# NegativeRegulator.net
KiCad netlist of a schematic drawn in Altium Designer
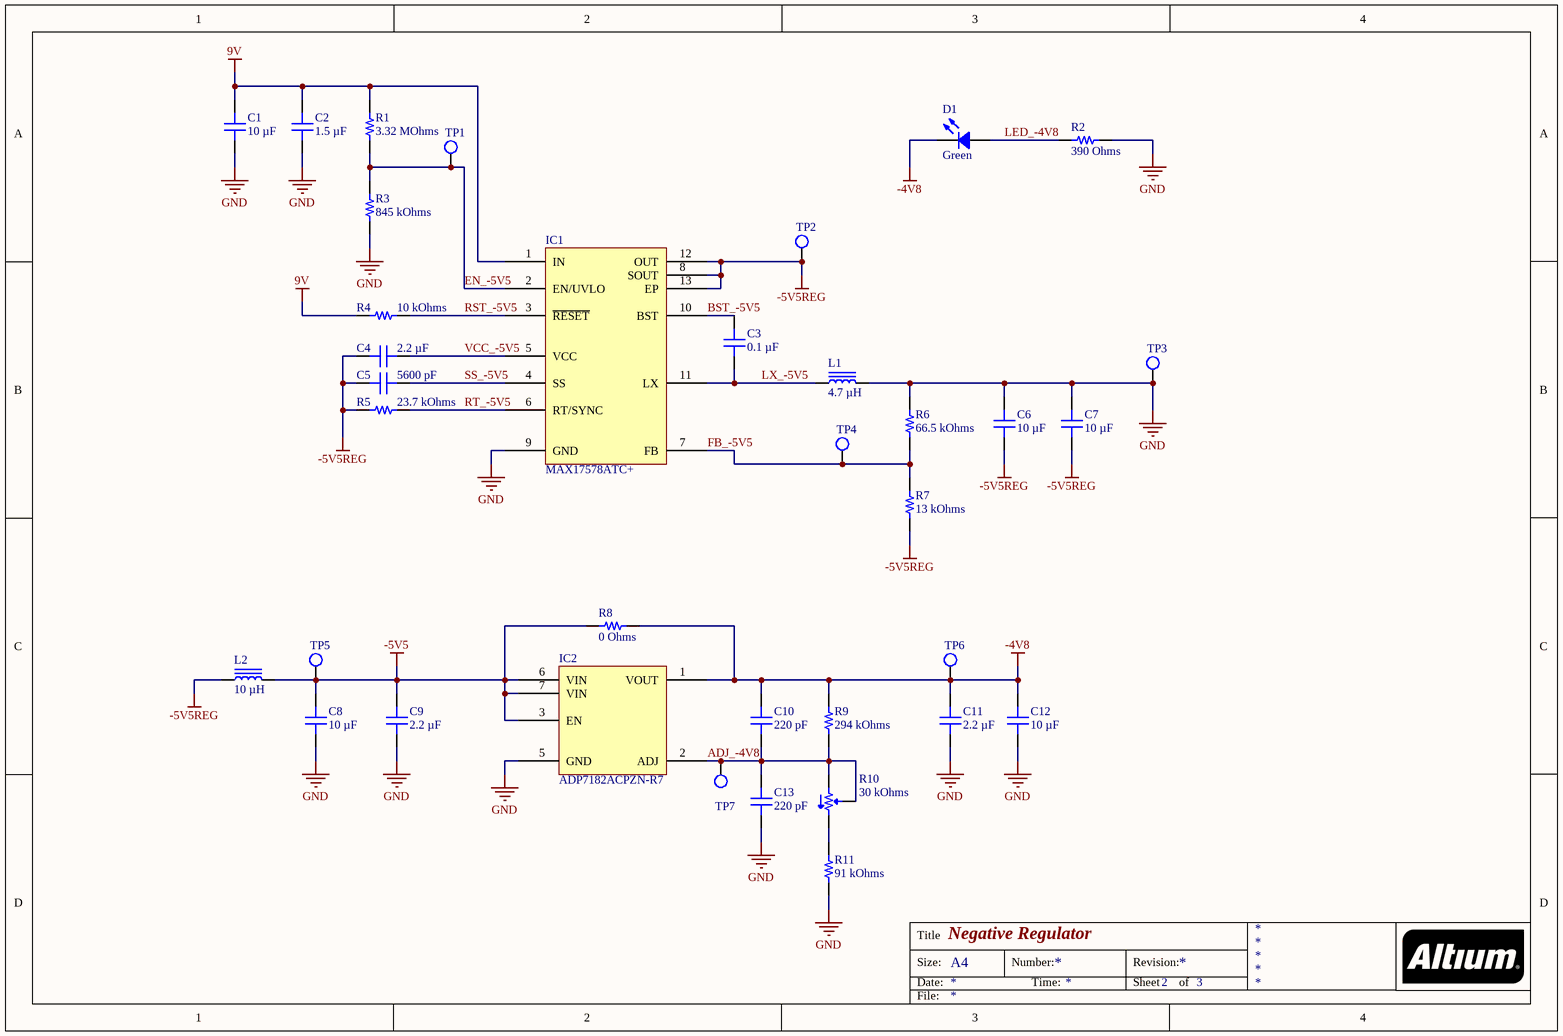
[diagram p0: NegativeRegulator.SchDoc]

(export (version "E")
  (design (tool "Eeschema 10.0.6"))
  (components
    (comp (ref "C1")
      (value "10 µF")
      (footprint "CAP 1206_3216 - 0.8MM")
      (description "CAP CER 10UF 35V X5R 1206")
      (fields (field (name "PART NUMBER") "GMK316BJ106KL-T") (field (name "MANUFACTURER") "Taiyo Yuden"))
      (libsource (lib "altiumlibrary.com") (part "Capacitor"))
    )
    (comp (ref "C2")
      (value "1.5 µF")
      (footprint "CAP 1206_3216 - 0.8MM")
      (description "CAP CER 1.5UF 16V X7R 1206")
      (fields (field (name "PART NUMBER") "C1206C155K4RAC7800") (field (name "MANUFACTURER") "KEMET"))
      (libsource (lib "altiumlibrary.com") (part "Capacitor"))
    )
    (comp (ref "C3")
      (value "0.1 µF")
      (footprint "CAP 0603_1608")
      (description "CAP CER 0.1UF 16V X7R 0603")
      (fields
        (field (name "PART NUMBER") "CL10B104KO8NNNC")
        (field (name "MANUFACTURER") "Samsung Electro-Mechanics")
      )
      (libsource (lib "altiumlibrary.com") (part "Capacitor"))
    )
    (comp (ref "C4")
      (value "2.2 µF")
      (footprint "CAP 0805_2012")
      (description "CAP CER 2.2UF 25V X7R 0805")
      (fields
        (field (name "PART NUMBER") "GRM21BR71E225KE11L")
        (field (name "MANUFACTURER") "Murata Electronics")
      )
      (libsource (lib "altiumlibrary.com") (part "Capacitor"))
    )
    (comp (ref "C5")
      (value "5600 pF")
      (footprint "CAP 0603_1608")
      (description "CAP CER 5600PF 50V X7R 0603")
      (fields (field (name "PART NUMBER") "C0603C562K5RAC7867") (field (name "MANUFACTURER") "KEMET"))
      (libsource (lib "altiumlibrary.com") (part "Capacitor"))
    )
    (comp (ref "C6")
      (value "10 µF")
      (footprint "CAP 1206_3216 - 0.8MM")
      (description "CAP CER 10UF 35V X5R 1206")
      (fields (field (name "PART NUMBER") "GMK316BJ106KL-T") (field (name "MANUFACTURER") "Taiyo Yuden"))
      (libsource (lib "altiumlibrary.com") (part "Capacitor"))
    )
    (comp (ref "C7")
      (value "10 µF")
      (footprint "CAP 1206_3216 - 0.8MM")
      (description "CAP CER 10UF 35V X5R 1206")
      (fields (field (name "PART NUMBER") "GMK316BJ106KL-T") (field (name "MANUFACTURER") "Taiyo Yuden"))
      (libsource (lib "altiumlibrary.com") (part "Capacitor"))
    )
    (comp (ref "C8")
      (value "10 µF")
      (footprint "CAP 1206_3216 - 0.8MM")
      (description "CAP CER 10UF 35V X5R 1206")
      (fields (field (name "PART NUMBER") "GMK316BJ106KL-T") (field (name "MANUFACTURER") "Taiyo Yuden"))
      (libsource (lib "altiumlibrary.com") (part "Capacitor"))
    )
    (comp (ref "C9")
      (value "2.2 µF")
      (footprint "CAP 0805_2012")
      (description "CAP CER 2.2UF 25V X7R 0805")
      (fields
        (field (name "PART NUMBER") "GRM21BR71E225KE11L")
        (field (name "MANUFACTURER") "Murata Electronics")
      )
      (libsource (lib "altiumlibrary.com") (part "Capacitor"))
    )
    (comp (ref "C10")
      (value "220 pF")
      (footprint "CAP 0603_1608")
      (description "CAP CER 220PF 25V C0G/NPO 0603")
      (fields (field (name "PART NUMBER") "CC0603JRNPO8BN221") (field (name "MANUFACTURER") "Yageo"))
      (libsource (lib "altiumlibrary.com") (part "Capacitor"))
    )
    (comp (ref "C11")
      (value "2.2 µF")
      (footprint "CAP 0805_2012")
      (description "CAP CER 2.2UF 25V X7R 0805")
      (fields
        (field (name "PART NUMBER") "GRM21BR71E225KE11L")
        (field (name "MANUFACTURER") "Murata Electronics")
      )
      (libsource (lib "altiumlibrary.com") (part "Capacitor"))
    )
    (comp (ref "C12")
      (value "10 µF")
      (footprint "CAP 1206_3216 - 0.8MM")
      (description "CAP CER 10UF 35V X5R 1206")
      (fields (field (name "PART NUMBER") "GMK316BJ106KL-T") (field (name "MANUFACTURER") "Taiyo Yuden"))
      (libsource (lib "altiumlibrary.com") (part "Capacitor"))
    )
    (comp (ref "C13")
      (value "220 pF")
      (footprint "CAP 0603_1608")
      (description "CAP CER 220PF 25V C0G/NPO 0603")
      (fields (field (name "PART NUMBER") "CC0603JRNPO8BN221") (field (name "MANUFACTURER") "Yageo"))
      (libsource (lib "altiumlibrary.com") (part "Capacitor"))
    )
    (comp (ref "D1")
      (value "Green")
      (footprint "LED 0805_2012 GREEN")
      (description "LED GREEN CLEAR CHIP SMD")
      (fields (field (name "PART NUMBER") "APHCM2012CGCK-F01") (field (name "MANUFACTURER") "Kingbright"))
      (libsource (lib "altiumlibrary.com") (part "LED"))
    )
    (comp (ref "IC1")
      (value "MAX17578ATC+")
      (footprint "MAXIM TDFN-12 3X3MM TD1233+1")
      (description "4.5V TO 60V, 1A HIGH-EFFICIENCY,")
      (fields (field (name "MANUFACTURER") "Analog Devices Inc./Maxim Integrated"))
      (libsource (lib "altiumlibrary.com") (part "MAXIM MAX17578"))
    )
    (comp (ref "IC2")
      (value "ADP7182ACPZN-R7")
      (footprint "AD LFCSP-6 2X2MM CP-6-3")
      (description "IC REG LIN NEG ADJ 200MA 6LFCSP")
      (fields (field (name "MANUFACTURER") "Analog Devices Inc."))
      (libsource (lib "altiumlibrary.com") (part "AD ADP7182 LFCSP6 ADJ"))
    )
    (comp (ref "L1")
      (value "4.7 µH")
      (footprint "WURTH WE-HCI 7040")
      (description "FIXED IND 4.7UH 6A 19.5 MOHM SMD")
      (fields (field (name "PART NUMBER") "744311470") (field (name "MANUFACTURER") "Würth Elektronik"))
      (libsource (lib "altiumlibrary.com") (part "Inductor"))
    )
    (comp (ref "L2")
      (value "10 µH")
      (footprint "TAIYO YUDEN NR4018")
      (description "FIXED IND 10UH 840MA 216MOHM SMD")
      (fields (field (name "PART NUMBER") "NR4018T100M") (field (name "MANUFACTURER") "Taiyo Yuden"))
      (libsource (lib "altiumlibrary.com") (part "Inductor"))
    )
    (comp (ref "R1")
      (value "3.32 MOhms")
      (footprint "RES 0603_1608")
      (description "RES 3.32M OHM 1% 1/10W 0603")
      (fields (field (name "PART NUMBER") "RC0603FR-073M32L") (field (name "MANUFACTURER") "Yageo"))
      (libsource (lib "altiumlibrary.com") (part "Resistor"))
    )
    (comp (ref "R2")
      (value "390 Ohms")
      (footprint "RES 0805_2012")
      (description "RES SMD 390 OHM 1% 1/8W 0805")
      (fields
        (field (name "PART NUMBER") "CRG0805F390R")
        (field (name "MANUFACTURER") "TE Connectivity Passive Product")
      )
      (libsource (lib "altiumlibrary.com") (part "Resistor"))
    )
    (comp (ref "R3")
      (value "845 kOhms")
      (footprint "RES 0603_1608")
      (description "RES 845K OHM 1% 1/10W 0603")
      (fields (field (name "PART NUMBER") "RC0603FR-07845KL") (field (name "MANUFACTURER") "Yageo"))
      (libsource (lib "altiumlibrary.com") (part "Resistor"))
    )
    (comp (ref "R4")
      (value "10 kOhms")
      (footprint "RES 0603_1608")
      (description "RES 10K OHM 1% 1/10W 0603")
      (fields (field (name "PART NUMBER") "RC0603FR-0710KL") (field (name "MANUFACTURER") "Yageo"))
      (libsource (lib "altiumlibrary.com") (part "Resistor"))
    )
    (comp (ref "R5")
      (value "23.7 kOhms")
      (footprint "RES 0603_1608")
      (description "RES 23.7K OHM 1% 1/10W 0603")
      (fields (field (name "PART NUMBER") "RC0603FR-0723K7L") (field (name "MANUFACTURER") "Yageo"))
      (libsource (lib "altiumlibrary.com") (part "Resistor"))
    )
    (comp (ref "R6")
      (value "66.5 kOhms")
      (footprint "RES 0603_1608")
      (description "RES SMD 66.5K OHM 1% 1/10W 0603")
      (fields
        (field (name "PART NUMBER") "ERJ-3EKF6652V")
        (field (name "MANUFACTURER") "Panasonic Electronic Components")
      )
      (libsource (lib "altiumlibrary.com") (part "Resistor"))
    )
    (comp (ref "R7")
      (value "13 kOhms")
      (footprint "RES 0603_1608")
      (description "RES SMD 13K OHM 5% 1/10W 0603")
      (fields
        (field (name "PART NUMBER") "ERJ-3GEYJ133V")
        (field (name "MANUFACTURER") "Panasonic Electronic Components")
      )
      (libsource (lib "altiumlibrary.com") (part "Resistor"))
    )
    (comp (ref "R8")
      (value "0 Ohms")
      (footprint "RES 0805_2012")
      (description "RES 0 OHM JUMPER 1/4W 0805")
      (fields (field (name "PART NUMBER") "RC0805JR-7W0RL") (field (name "MANUFACTURER") "Yageo"))
      (libsource (lib "altiumlibrary.com") (part "Resistor"))
    )
    (comp (ref "R9")
      (value "294 kOhms")
      (footprint "RES 0603_1608")
      (description "RES SMD 294K OHM 0.1% 1/10W 0603")
      (fields
        (field (name "PART NUMBER") "ERA-3AEB2943V")
        (field (name "MANUFACTURER") "Panasonic Electronic Components")
      )
      (libsource (lib "altiumlibrary.com") (part "Resistor"))
    )
    (comp (ref "R10")
      (value "30 kOhms")
      (footprint "POT BOURNS TRIMPOT TC33")
      (description "TRIMMER 30K OHM 0.1W J LEAD TOP")
      (fields (field (name "PART NUMBER") "TC33X-2-303E") (field (name "MANUFACTURER") "Bourns Inc."))
      (libsource (lib "altiumlibrary.com") (part "Potentiometer"))
    )
    (comp (ref "R11")
      (value "91 kOhms")
      (footprint "RES 0603_1608")
      (description "RES 91K OHM 1% 1/10W 0603")
      (fields (field (name "PART NUMBER") "RC0603FR-0791KL") (field (name "MANUFACTURER") "Yageo"))
      (libsource (lib "altiumlibrary.com") (part "Resistor"))
    )
    (comp (ref "TP1")
      (value "Test Point")
      (footprint "TestPoint-1.5mm")
      (libsource (lib "Original Circuit") (part "Test Point"))
    )
    (comp (ref "TP2")
      (value "Test Point")
      (footprint "TestPoint-1.5mm")
      (libsource (lib "Original Circuit") (part "Test Point"))
    )
    (comp (ref "TP3")
      (value "Test Point")
      (footprint "TestPoint-1.5mm")
      (libsource (lib "Original Circuit") (part "Test Point"))
    )
    (comp (ref "TP4")
      (value "Test Point")
      (footprint "TestPoint-1.5mm")
      (libsource (lib "Original Circuit") (part "Test Point"))
    )
    (comp (ref "TP5")
      (value "Test Point")
      (footprint "TestPoint-1.5mm")
      (libsource (lib "Original Circuit") (part "Test Point"))
    )
    (comp (ref "TP6")
      (value "Test Point")
      (footprint "TestPoint-1.5mm")
      (libsource (lib "Original Circuit") (part "Test Point"))
    )
    (comp (ref "TP7")
      (value "Test Point")
      (footprint "TestPoint-1.5mm")
      (libsource (lib "Original Circuit") (part "Test Point"))
    )
  )
  (nets
    (net (code "1") (name "-4V8") (class "Default")
      (node (ref "C10") (pin "2") (pinfunction "2_2") (pintype "passive"))
      (node (ref "C11") (pin "2") (pinfunction "2_2") (pintype "passive"))
      (node (ref "C12") (pin "2") (pinfunction "2_2") (pintype "passive"))
      (node (ref "D1") (pin "2") (pinfunction "2_2") (pintype "passive"))
      (node (ref "IC2") (pin "1") (pinfunction "VOUT_1") (pintype "passive"))
      (node (ref "R8") (pin "2") (pinfunction "2_2") (pintype "passive"))
      (node (ref "R9") (pin "2") (pinfunction "2_2") (pintype "passive"))
      (node (ref "TP6") (pin "1") (pinfunction "TP_1") (pintype "passive"))
    )
    (net (code "2") (name "-5V5") (class "Default")
      (node (ref "C8") (pin "2") (pinfunction "2_2") (pintype "passive"))
      (node (ref "C9") (pin "2") (pinfunction "2_2") (pintype "passive"))
      (node (ref "IC2") (pin "3") (pinfunction "EN_3") (pintype "passive"))
      (node (ref "IC2") (pin "6") (pinfunction "VIN_6") (pintype "passive"))
      (node (ref "IC2") (pin "7") (pinfunction "VIN_7") (pintype "passive"))
      (node (ref "L2") (pin "2") (pinfunction "2_2") (pintype "passive"))
      (node (ref "R8") (pin "1") (pinfunction "1_1") (pintype "passive"))
      (node (ref "TP5") (pin "1") (pinfunction "TP_1") (pintype "passive"))
    )
    (net (code "3") (name "-5V5REG") (class "Default")
      (node (ref "C4") (pin "1") (pinfunction "1_1") (pintype "passive"))
      (node (ref "C5") (pin "1") (pinfunction "1_1") (pintype "passive"))
      (node (ref "C6") (pin "1") (pinfunction "1_1") (pintype "passive"))
      (node (ref "C7") (pin "1") (pinfunction "1_1") (pintype "passive"))
      (node (ref "IC1") (pin "12") (pinfunction "OUT_12") (pintype "passive"))
      (node (ref "IC1") (pin "13") (pinfunction "EP_13") (pintype "passive"))
      (node (ref "IC1") (pin "8") (pinfunction "SOUT_8") (pintype "passive"))
      (node (ref "L2") (pin "1") (pinfunction "1_1") (pintype "passive"))
      (node (ref "R5") (pin "1") (pinfunction "1_1") (pintype "passive"))
      (node (ref "R7") (pin "1") (pinfunction "1_1") (pintype "passive"))
      (node (ref "TP2") (pin "1") (pinfunction "TP_1") (pintype "passive"))
    )
    (net (code "4") (name "/ADJ_-4V8") (class "Default")
      (node (ref "C10") (pin "1") (pinfunction "1_1") (pintype "passive"))
      (node (ref "C13") (pin "2") (pinfunction "2_2") (pintype "passive"))
      (node (ref "IC2") (pin "2") (pinfunction "ADJ_2") (pintype "passive"))
      (node (ref "R10") (pin "1") (pinfunction "1_1") (pintype "passive"))
      (node (ref "R10") (pin "2") (pinfunction "2_2") (pintype "passive"))
      (node (ref "R9") (pin "1") (pinfunction "1_1") (pintype "passive"))
      (node (ref "TP7") (pin "1") (pinfunction "TP_1") (pintype "passive"))
    )
    (net (code "5") (name "/BST_-5V5") (class "Default")
      (node (ref "C3") (pin "2") (pinfunction "2_2") (pintype "passive"))
      (node (ref "IC1") (pin "10") (pinfunction "BST_10") (pintype "passive"))
    )
    (net (code "6") (name "/EN_-5V5") (class "Default")
      (node (ref "IC1") (pin "2") (pinfunction "EN/UVLO_2") (pintype "passive"))
      (node (ref "R1") (pin "1") (pinfunction "1_1") (pintype "passive"))
      (node (ref "R3") (pin "2") (pinfunction "2_2") (pintype "passive"))
      (node (ref "TP1") (pin "1") (pinfunction "TP_1") (pintype "passive"))
    )
    (net (code "7") (name "/FB_-5V5") (class "Default")
      (node (ref "IC1") (pin "7") (pinfunction "FB_7") (pintype "passive"))
      (node (ref "R6") (pin "1") (pinfunction "1_1") (pintype "passive"))
      (node (ref "R7") (pin "2") (pinfunction "2_2") (pintype "passive"))
      (node (ref "TP4") (pin "1") (pinfunction "TP_1") (pintype "passive"))
    )
    (net (code "8") (name "/LED_-4V8") (class "Default")
      (node (ref "D1") (pin "1") (pinfunction "1_1") (pintype "passive"))
      (node (ref "R2") (pin "1") (pinfunction "1_1") (pintype "passive"))
    )
    (net (code "9") (name "/LX_-5V5") (class "Default")
      (node (ref "C3") (pin "1") (pinfunction "1_1") (pintype "passive"))
      (node (ref "IC1") (pin "11") (pinfunction "LX_11") (pintype "passive"))
      (node (ref "L1") (pin "1") (pinfunction "1_1") (pintype "passive"))
    )
    (net (code "10") (name "/RST_-5V5") (class "Default")
      (node (ref "IC1") (pin "3") (pinfunction "~{RESET}_3") (pintype "passive"))
      (node (ref "R4") (pin "2") (pinfunction "2_2") (pintype "passive"))
    )
    (net (code "11") (name "/RT_-5V5") (class "Default")
      (node (ref "IC1") (pin "6") (pinfunction "RT/SYNC_6") (pintype "passive"))
      (node (ref "R5") (pin "2") (pinfunction "2_2") (pintype "passive"))
    )
    (net (code "12") (name "/SS_-5V5") (class "Default")
      (node (ref "C5") (pin "2") (pinfunction "2_2") (pintype "passive"))
      (node (ref "IC1") (pin "4") (pinfunction "SS_4") (pintype "passive"))
    )
    (net (code "13") (name "/VCC_-5V5") (class "Default")
      (node (ref "C4") (pin "2") (pinfunction "2_2") (pintype "passive"))
      (node (ref "IC1") (pin "5") (pinfunction "VCC_5") (pintype "passive"))
    )
    (net (code "14") (name "9V") (class "Default")
      (node (ref "C1") (pin "2") (pinfunction "2_2") (pintype "passive"))
      (node (ref "C2") (pin "2") (pinfunction "2_2") (pintype "passive"))
      (node (ref "IC1") (pin "1") (pinfunction "IN_1") (pintype "passive"))
      (node (ref "R1") (pin "2") (pinfunction "2_2") (pintype "passive"))
      (node (ref "R4") (pin "1") (pinfunction "1_1") (pintype "passive"))
    )
    (net (code "15") (name "GND") (class "Default")
      (node (ref "C1") (pin "1") (pinfunction "1_1") (pintype "passive"))
      (node (ref "C11") (pin "1") (pinfunction "1_1") (pintype "passive"))
      (node (ref "C12") (pin "1") (pinfunction "1_1") (pintype "passive"))
      (node (ref "C13") (pin "1") (pinfunction "1_1") (pintype "passive"))
      (node (ref "C2") (pin "1") (pinfunction "1_1") (pintype "passive"))
      (node (ref "C6") (pin "2") (pinfunction "2_2") (pintype "passive"))
      (node (ref "C7") (pin "2") (pinfunction "2_2") (pintype "passive"))
      (node (ref "C8") (pin "1") (pinfunction "1_1") (pintype "passive"))
      (node (ref "C9") (pin "1") (pinfunction "1_1") (pintype "passive"))
      (node (ref "IC1") (pin "9") (pinfunction "GND_9") (pintype "passive"))
      (node (ref "IC2") (pin "5") (pinfunction "GND_5") (pintype "passive"))
      (node (ref "L1") (pin "2") (pinfunction "2_2") (pintype "passive"))
      (node (ref "R11") (pin "1") (pinfunction "1_1") (pintype "passive"))
      (node (ref "R2") (pin "2") (pinfunction "2_2") (pintype "passive"))
      (node (ref "R3") (pin "1") (pinfunction "1_1") (pintype "passive"))
      (node (ref "R6") (pin "2") (pinfunction "2_2") (pintype "passive"))
      (node (ref "TP3") (pin "1") (pinfunction "TP_1") (pintype "passive"))
    )
    (net (code "16") (name "Net-(R10-Pad3)") (class "Default")
      (node (ref "R10") (pin "3") (pinfunction "3_3") (pintype "passive"))
      (node (ref "R11") (pin "2") (pinfunction "2_2") (pintype "passive"))
    )
  )
)
